# vocore_dock.net
KiCad netlist of a schematic drawn in EAGLE
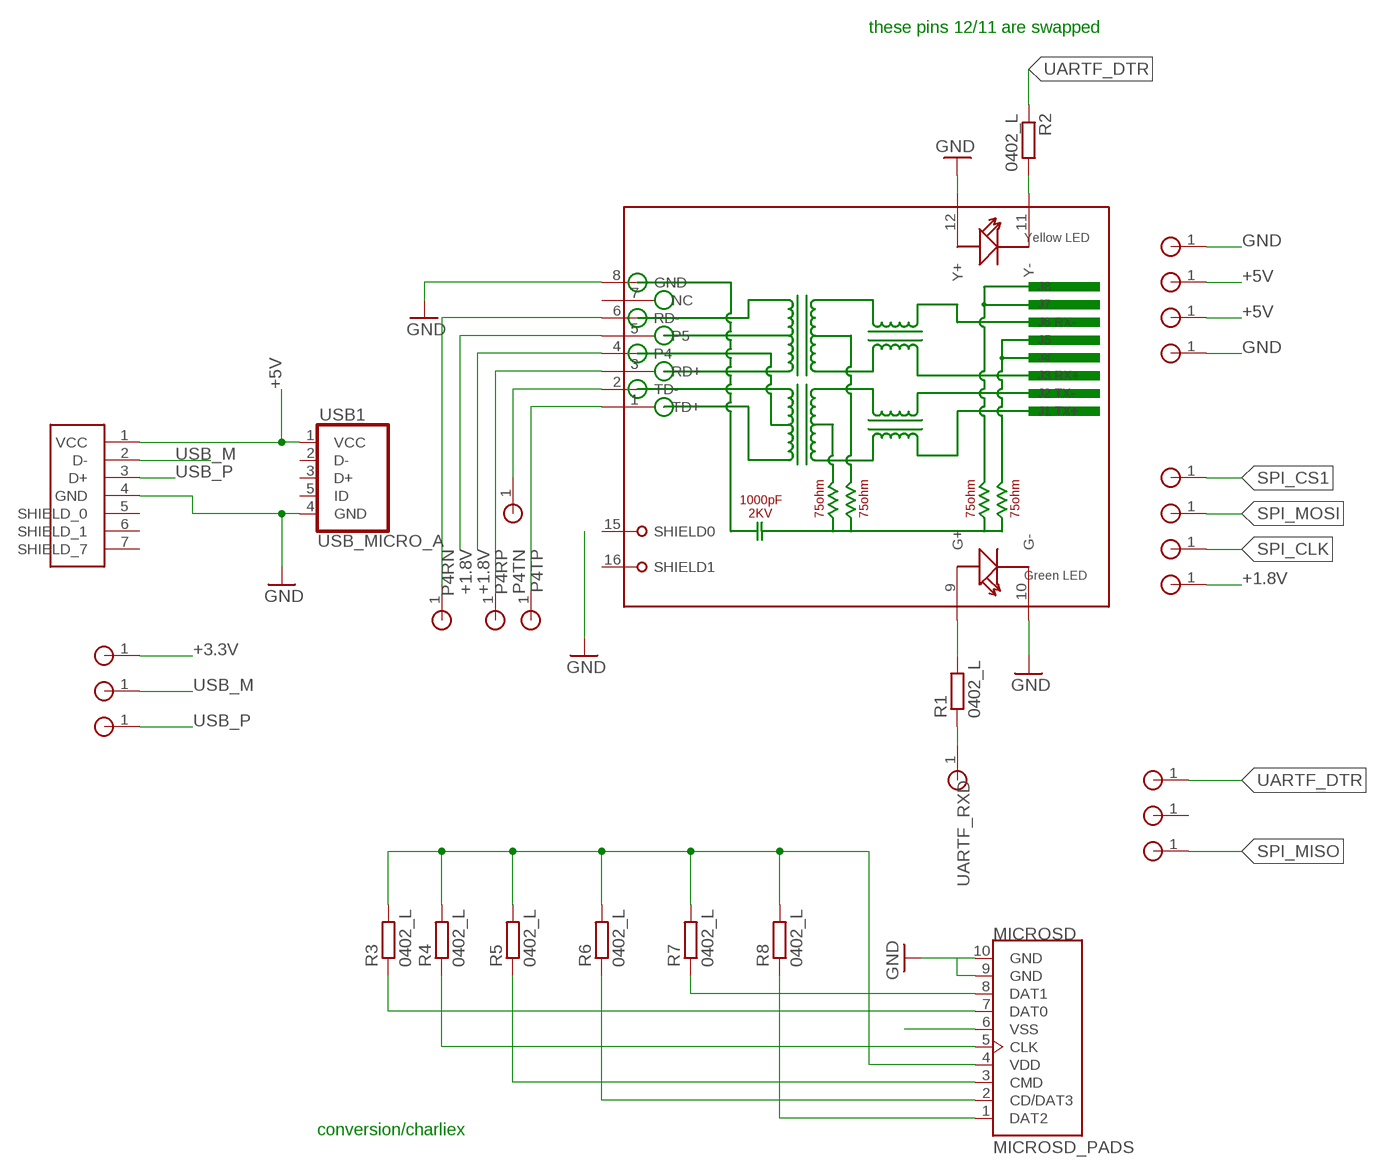
[diagram p0: schematic, sheet 1]

(export (version "E")
  (design (tool "Eeschema 10.0.6"))
  (components
    (comp (ref "MICROSD")
      (value "MICROSD_PADS")
      (footprint "eagle-import:MICROSD_PADS_1PRIMARY")
      (libsource (lib "eagle-import") (part "MICROSD_PADS"))
    )
    (comp (ref "PB04")
      (value "PORT_1PIN")
      (footprint "eagle-import:PORT_1PIN_DECAL_1PRIMARY")
      (libsource (lib "eagle-import") (part "PORT_1PIN"))
    )
    (comp (ref "PB05")
      (value "PORT_1PIN")
      (footprint "eagle-import:PORT_1PIN_DECAL_1PRIMARY")
      (libsource (lib "eagle-import") (part "PORT_1PIN"))
    )
    (comp (ref "PB06")
      (value "PORT_1PIN")
      (footprint "eagle-import:PORT_1PIN_DECAL_1PRIMARY")
      (libsource (lib "eagle-import") (part "PORT_1PIN"))
    )
    (comp (ref "PB07")
      (value "PORT_1PIN")
      (footprint "eagle-import:PORT_1PIN_DECAL_1PRIMARY")
      (libsource (lib "eagle-import") (part "PORT_1PIN"))
    )
    (comp (ref "PB12")
      (value "PORT_1PIN")
      (footprint "eagle-import:PORT_1PIN_DECAL_1PRIMARY")
      (libsource (lib "eagle-import") (part "PORT_1PIN"))
    )
    (comp (ref "PB13")
      (value "PORT_1PIN")
      (footprint "eagle-import:PORT_1PIN_DECAL_1PRIMARY")
      (libsource (lib "eagle-import") (part "PORT_1PIN"))
    )
    (comp (ref "PB14")
      (value "PORT_1PIN")
      (footprint "eagle-import:PORT_1PIN_DECAL_1PRIMARY")
      (libsource (lib "eagle-import") (part "PORT_1PIN"))
    )
    (comp (ref "PB15")
      (value "PORT_1PIN")
      (footprint "eagle-import:PORT_1PIN_DECAL_1PRIMARY")
      (libsource (lib "eagle-import") (part "PORT_1PIN"))
    )
    (comp (ref "PB16")
      (value "PORT_1PIN")
      (footprint "eagle-import:PORT_1PIN_DECAL_1PRIMARY")
      (libsource (lib "eagle-import") (part "PORT_1PIN"))
    )
    (comp (ref "PB17")
      (value "PORT_1PIN")
      (footprint "eagle-import:PORT_1PIN_DECAL_1PRIMARY")
      (libsource (lib "eagle-import") (part "PORT_1PIN"))
    )
    (comp (ref "PB18")
      (value "PORT_1PIN")
      (footprint "eagle-import:PORT_1PIN_DECAL_1PRIMARY")
      (libsource (lib "eagle-import") (part "PORT_1PIN"))
    )
    (comp (ref "PL05")
      (value "PORT_1PIN")
      (footprint "eagle-import:PORT_1PIN_DECAL_1PRIMARY")
      (libsource (lib "eagle-import") (part "PORT_1PIN"))
    )
    (comp (ref "PL06")
      (value "PORT_1PIN")
      (footprint "eagle-import:PORT_1PIN_DECAL_1PRIMARY")
      (libsource (lib "eagle-import") (part "PORT_1PIN"))
    )
    (comp (ref "PL07")
      (value "PORT_1PIN")
      (footprint "eagle-import:PORT_1PIN_DECAL_1PRIMARY")
      (libsource (lib "eagle-import") (part "PORT_1PIN"))
    )
    (comp (ref "PL08")
      (value "PORT_1PIN")
      (footprint "eagle-import:PORT_1PIN_DECAL_1PRIMARY")
      (libsource (lib "eagle-import") (part "PORT_1PIN"))
    )
    (comp (ref "PT01")
      (value "PORT_1PIN")
      (footprint "eagle-import:PORT_1PIN_DECAL_1PRIMARY")
      (libsource (lib "eagle-import") (part "PORT_1PIN"))
    )
    (comp (ref "PT02")
      (value "PORT_1PIN")
      (footprint "eagle-import:PORT_1PIN_DECAL_1PRIMARY")
      (libsource (lib "eagle-import") (part "PORT_1PIN"))
    )
    (comp (ref "PT03")
      (value "PORT_1PIN")
      (footprint "eagle-import:PORT_1PIN_DECAL_1PRIMARY")
      (libsource (lib "eagle-import") (part "PORT_1PIN"))
    )
    (comp (ref "PT04")
      (value "PORT_1PIN")
      (footprint "eagle-import:PORT_1PIN_DECAL_1PRIMARY")
      (libsource (lib "eagle-import") (part "PORT_1PIN"))
    )
    (comp (ref "R1")
      (value "0402_L")
      (footprint "eagle-import:0402_L_1PRIMARY")
      (libsource (lib "eagle-import") (part "0402_L"))
    )
    (comp (ref "R2")
      (value "0402_L")
      (footprint "eagle-import:0402_L_1PRIMARY")
      (libsource (lib "eagle-import") (part "0402_L"))
    )
    (comp (ref "R3")
      (value "0402_L")
      (footprint "eagle-import:0402_L_1PRIMARY")
      (libsource (lib "eagle-import") (part "0402_L"))
    )
    (comp (ref "R4")
      (value "0402_L")
      (footprint "eagle-import:0402_L_1PRIMARY")
      (libsource (lib "eagle-import") (part "0402_L"))
    )
    (comp (ref "R5")
      (value "0402_L")
      (footprint "eagle-import:0402_L_1PRIMARY")
      (libsource (lib "eagle-import") (part "0402_L"))
    )
    (comp (ref "R6")
      (value "0402_L")
      (footprint "eagle-import:0402_L_1PRIMARY")
      (libsource (lib "eagle-import") (part "0402_L"))
    )
    (comp (ref "R7")
      (value "0402_L")
      (footprint "eagle-import:0402_L_1PRIMARY")
      (libsource (lib "eagle-import") (part "0402_L"))
    )
    (comp (ref "R8")
      (value "0402_L")
      (footprint "eagle-import:0402_L_1PRIMARY")
      (libsource (lib "eagle-import") (part "0402_L"))
    )
    (comp (ref "RJ45")
      (value "RJ45ALED")
      (footprint "eagle-import:RJ45ALED_1PRIMARY")
      (libsource (lib "eagle-import") (part "HR911105AHR911105A"))
    )
    (comp (ref "USB1")
      (value "USB_MICRO_A")
      (footprint "eagle-import:USB_MICRO_A_1PRIMARY")
      (libsource (lib "eagle-import") (part "USB_MICRO_AUSB_MICRO_A"))
    )
    (comp (ref "USB2")
      (value "USB_FULL_TALL")
      (footprint "eagle-import:USB_FULL_TALL_1PRIMARY")
      (libsource (lib "eagle-import") (part "USB_FULL_TALL"))
    )
  )
  (nets
    (net (code "1") (name "/+1.8V") (class "Default")
      (node (ref "PL05") (pin "1") (pinfunction "P$1_1") (pintype "bidirectional"))
      (node (ref "RJ45") (pin "4") (pinfunction "P4_4") (pintype "bidirectional"))
      (node (ref "RJ45") (pin "5") (pinfunction "P5_5") (pintype "bidirectional"))
    )
    (net (code "2") (name "/+3.3V") (class "Default")
      (node (ref "MICROSD") (pin "4") (pinfunction "VDD_4") (pintype "bidirectional"))
      (node (ref "PB18") (pin "1") (pinfunction "P$1_1") (pintype "bidirectional"))
      (node (ref "R3") (pin "2") (pinfunction "2_2") (pintype "passive"))
      (node (ref "R4") (pin "2") (pinfunction "2_2") (pintype "passive"))
      (node (ref "R5") (pin "2") (pinfunction "2_2") (pintype "passive"))
      (node (ref "R6") (pin "2") (pinfunction "2_2") (pintype "passive"))
      (node (ref "R7") (pin "2") (pinfunction "2_2") (pintype "passive"))
      (node (ref "R8") (pin "2") (pinfunction "2_2") (pintype "passive"))
    )
    (net (code "3") (name "/+5V") (class "Default")
      (node (ref "PT02") (pin "1") (pinfunction "P$1_1") (pintype "bidirectional"))
      (node (ref "PT03") (pin "1") (pinfunction "P$1_1") (pintype "bidirectional"))
      (node (ref "USB1") (pin "1") (pinfunction "VCC_1") (pintype "bidirectional"))
      (node (ref "USB2") (pin "1") (pinfunction "VCC_1") (pintype "power_in"))
    )
    (net (code "4") (name "/P4RN") (class "Default")
      (node (ref "PB15") (pin "1") (pinfunction "P$1_1") (pintype "bidirectional"))
      (node (ref "RJ45") (pin "6") (pinfunction "RD-_6") (pintype "bidirectional"))
    )
    (net (code "5") (name "/P4RP") (class "Default")
      (node (ref "PB14") (pin "1") (pinfunction "P$1_1") (pintype "bidirectional"))
      (node (ref "RJ45") (pin "3") (pinfunction "RD+_3") (pintype "bidirectional"))
    )
    (net (code "6") (name "/P4TN") (class "Default")
      (node (ref "PB12") (pin "1") (pinfunction "P$1_1") (pintype "bidirectional"))
      (node (ref "RJ45") (pin "2") (pinfunction "TD-_2") (pintype "bidirectional"))
    )
    (net (code "7") (name "/P4TP") (class "Default")
      (node (ref "PB13") (pin "1") (pinfunction "P$1_1") (pintype "bidirectional"))
      (node (ref "RJ45") (pin "1") (pinfunction "TD+_1") (pintype "bidirectional"))
    )
    (net (code "8") (name "/UARTF_RXD") (class "Default")
      (node (ref "PB04") (pin "1") (pinfunction "P$1_1") (pintype "bidirectional"))
      (node (ref "R1") (pin "1") (pinfunction "1_1") (pintype "passive"))
    )
    (net (code "9") (name "/USB_M") (class "Default")
      (node (ref "PB16") (pin "1") (pinfunction "P$1_1") (pintype "bidirectional"))
      (node (ref "USB2") (pin "2") (pinfunction "D-_2") (pintype "bidirectional"))
    )
    (net (code "10") (name "/USB_P") (class "Default")
      (node (ref "PB17") (pin "1") (pinfunction "P$1_1") (pintype "bidirectional"))
      (node (ref "USB2") (pin "3") (pinfunction "D+_3") (pintype "bidirectional"))
    )
    (net (code "11") (name "GND") (class "Default")
      (node (ref "MICROSD") (pin "10") (pinfunction "GND_10") (pintype "power_in"))
      (node (ref "MICROSD") (pin "6") (pinfunction "VSS_6") (pintype "power_in"))
      (node (ref "MICROSD") (pin "9") (pinfunction "GND_9") (pintype "power_in"))
      (node (ref "PT01") (pin "1") (pinfunction "P$1_1") (pintype "bidirectional"))
      (node (ref "PT04") (pin "1") (pinfunction "P$1_1") (pintype "bidirectional"))
      (node (ref "RJ45") (pin "10") (pinfunction "G-_10") (pintype "bidirectional"))
      (node (ref "RJ45") (pin "12") (pinfunction "Y+_12") (pintype "bidirectional"))
      (node (ref "RJ45") (pin "8") (pinfunction "GND_8") (pintype "bidirectional"))
      (node (ref "USB1") (pin "4") (pinfunction "GND_4") (pintype "bidirectional"))
      (node (ref "USB2") (pin "4") (pinfunction "GND_4") (pintype "power_in"))
    )
    (net (code "12") (name "Net-(MICROSD-DAT1)") (class "Default")
      (node (ref "MICROSD") (pin "8") (pinfunction "DAT1_8") (pintype "bidirectional"))
      (node (ref "R7") (pin "1") (pinfunction "1_1") (pintype "passive"))
    )
    (net (code "13") (name "Net-(MICROSD-DAT2)") (class "Default")
      (node (ref "MICROSD") (pin "1") (pinfunction "DAT2_1") (pintype "bidirectional"))
      (node (ref "R8") (pin "1") (pinfunction "1_1") (pintype "passive"))
    )
    (net (code "14") (name "Net-(RJ45-G+)") (class "Default")
      (node (ref "R1") (pin "2") (pinfunction "2_2") (pintype "passive"))
      (node (ref "RJ45") (pin "9") (pinfunction "G+_9") (pintype "bidirectional"))
    )
    (net (code "15") (name "Net-(RJ45-Y-)") (class "Default")
      (node (ref "R2") (pin "2") (pinfunction "2_2") (pintype "passive"))
      (node (ref "RJ45") (pin "11") (pinfunction "Y-_11") (pintype "bidirectional"))
    )
    (net (code "16") (name "SPI_CLK") (class "Default")
      (node (ref "MICROSD") (pin "5") (pinfunction "CLK_5") (pintype "bidirectional"))
      (node (ref "PL06") (pin "1") (pinfunction "P$1_1") (pintype "bidirectional"))
      (node (ref "R4") (pin "1") (pinfunction "1_1") (pintype "passive"))
    )
    (net (code "17") (name "SPI_CS1") (class "Default")
      (node (ref "MICROSD") (pin "2") (pinfunction "CD/DAT3_2") (pintype "bidirectional"))
      (node (ref "PL08") (pin "1") (pinfunction "P$1_1") (pintype "bidirectional"))
      (node (ref "R6") (pin "1") (pinfunction "1_1") (pintype "passive"))
    )
    (net (code "18") (name "SPI_MISO") (class "Default")
      (node (ref "MICROSD") (pin "7") (pinfunction "DAT0_7") (pintype "bidirectional"))
      (node (ref "PB05") (pin "1") (pinfunction "P$1_1") (pintype "bidirectional"))
      (node (ref "R3") (pin "1") (pinfunction "1_1") (pintype "passive"))
    )
    (net (code "19") (name "SPI_MOSI") (class "Default")
      (node (ref "MICROSD") (pin "3") (pinfunction "CMD_3") (pintype "bidirectional"))
      (node (ref "PL07") (pin "1") (pinfunction "P$1_1") (pintype "bidirectional"))
      (node (ref "R5") (pin "1") (pinfunction "1_1") (pintype "passive"))
    )
    (net (code "20") (name "UARTF_DTR") (class "Default")
      (node (ref "PB07") (pin "1") (pinfunction "P$1_1") (pintype "bidirectional"))
      (node (ref "R2") (pin "1") (pinfunction "1_1") (pintype "passive"))
    )
    (net (code "21") (name "unconnected-(PB06-P$1-Pad1)") (class "Default")
      (node (ref "PB06") (pin "1") (pinfunction "P$1_1") (pintype "bidirectional"))
    )
    (net (code "22") (name "unconnected-(RJ45-NC-Pad7)") (class "Default")
      (node (ref "RJ45") (pin "7") (pinfunction "NC_7") (pintype "bidirectional"))
    )
    (net (code "23") (name "unconnected-(RJ45-SHIELD0-Pad15)") (class "Default")
      (node (ref "RJ45") (pin "15") (pinfunction "SHIELD0_15") (pintype "bidirectional"))
    )
    (net (code "24") (name "unconnected-(RJ45-SHIELD1-Pad16)") (class "Default")
      (node (ref "RJ45") (pin "16") (pinfunction "SHIELD1_16") (pintype "bidirectional"))
    )
    (net (code "25") (name "unconnected-(USB1-D+-Pad3)") (class "Default")
      (node (ref "USB1") (pin "3") (pinfunction "D+_3") (pintype "bidirectional"))
    )
    (net (code "26") (name "unconnected-(USB1-D--Pad2)") (class "Default")
      (node (ref "USB1") (pin "2") (pinfunction "D-_2") (pintype "bidirectional"))
    )
    (net (code "27") (name "unconnected-(USB1-ID-Pad5)") (class "Default")
      (node (ref "USB1") (pin "5") (pinfunction "ID_5") (pintype "bidirectional"))
    )
    (net (code "28") (name "unconnected-(USB2-SHIELD_0-Pad5)") (class "Default")
      (node (ref "USB2") (pin "5") (pinfunction "SHIELD_0_5") (pintype "bidirectional"))
    )
    (net (code "29") (name "unconnected-(USB2-SHIELD_1-Pad6)") (class "Default")
      (node (ref "USB2") (pin "6") (pinfunction "SHIELD_1_6") (pintype "bidirectional"))
    )
    (net (code "30") (name "unconnected-(USB2-SHIELD_7-Pad7)") (class "Default")
      (node (ref "USB2") (pin "7") (pinfunction "SHIELD_7_7") (pintype "bidirectional"))
    )
  )
)
